# 1.net
KiCad netlist of a schematic drawn in Altium Designer
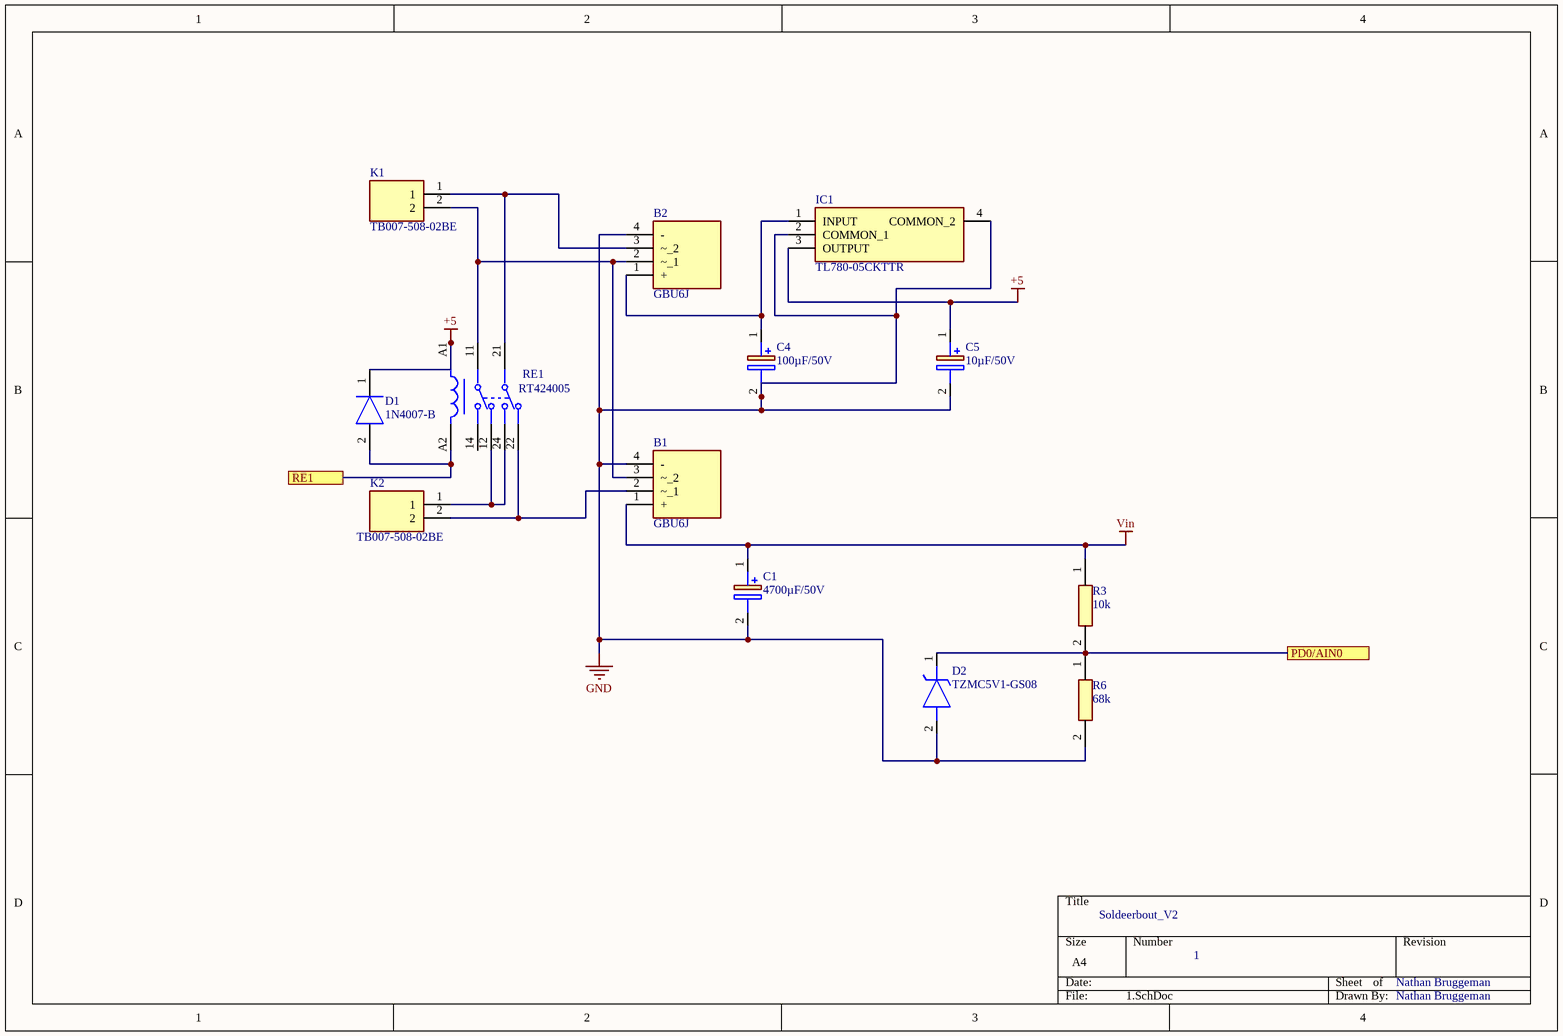
[diagram p0: 1.SchDoc]

(export (version "E")
  (design (tool "Eeschema 10.0.6"))
  (components
    (comp (ref "B1")
      (value "GBU6J")
      (footprint "GBU6J")
      (description "Bridge Rectifier")
      (libsource (lib "B1_B2") (part "GBU6J"))
    )
    (comp (ref "B2")
      (value "GBU6J")
      (footprint "GBU6J")
      (description "Bridge Rectifier")
      (libsource (lib "B1_B2") (part "GBU6J"))
    )
    (comp (ref "C1")
      (value "4700µF/50V")
      (footprint "CAPPRD1000W80D2200H3700")
      (description "Capacitor Polarised")
      (fields
        (field (name "MOUSER2 PART NUMBER") "80-ESK478M050AQ3AA")
        (field (name "MANUFACTURER_PART_NUMBER") "ESK478M050AQ3AA")
      )
      (libsource (lib "Condensator_4700µF_V2") (part "ESK478M050AQ3AA"))
    )
    (comp (ref "C4")
      (value "100µF/50V")
      (footprint "CAPPRD350W60D800H1250")
      (description "Capacitor Polarised")
      (fields (field (name "MANUFACTURER_PART_NUMBER") "ESK107M050AG3EA"))
      (libsource (lib "Condensator_100µF_V2") (part "ESK107M050AG3EA"))
    )
    (comp (ref "C5")
      (value "10µF/50V")
      (footprint "CAPPRD200W55D500H1200")
      (description "Capacitor Polarised")
      (fields
        (field (name "MOUSER2 PART NUMBER") "667-ECA-1HM100")
        (field (name "MANUFACTURER_PART_NUMBER") "ECA-1HM100")
      )
      (libsource (lib "Condensator_10µF_V2") (part "ECA-1HM100"))
    )
    (comp (ref "D1")
      (value "1N4007-B")
      (footprint "DIOAD1410W90L470D235")
      (description "Diode")
      (libsource (lib "D1") (part "1N4007-B"))
    )
    (comp (ref "D2")
      (value "TZMC5V1-GS08")
      (footprint "TZMC5V1GS08")
      (description "Zener Diode")
      (libsource (lib "D2") (part "TZMC5V1-GS08"))
    )
    (comp (ref "IC1")
      (value "TL780-05CKTTR")
      (footprint "TL78005CKTTR")
      (description "Integrated Circuit")
      (libsource (lib "IC1") (part "TL780-05CKTTR"))
    )
    (comp (ref "K1")
      (value "TB007-508-02BE")
      (footprint "TB00750802BE")
      (description "Connector")
      (fields (field (name "MOUSER2 PART NUMBER") "490-TB007-508-02BE"))
      (libsource (lib "K1_K2_K3_K8") (part "TB007-508-02BE"))
    )
    (comp (ref "K2")
      (value "TB007-508-02BE")
      (footprint "TB00750802BE")
      (description "Connector")
      (fields (field (name "MOUSER2 PART NUMBER") "490-TB007-508-02BE"))
      (libsource (lib "K1_K2_K3_K8") (part "TB007-508-02BE"))
    )
    (comp (ref "R3")
      (value "10k")
      (footprint "0805")
      (description "Resistor")
      (fields (field (name "MANUFACTURER_PART_NUMBER") "CFN0805-FZ-R030ELF"))
      (libsource (lib "Weerstand_0805") (part "CFN0805-FZ-R030ELF"))
    )
    (comp (ref "R6")
      (value "68k")
      (footprint "0805")
      (description "Resistor")
      (fields (field (name "MANUFACTURER_PART_NUMBER") "CFN0805-FZ-R030ELF"))
      (libsource (lib "Weerstand_0805") (part "CFN0805-FZ-R030ELF"))
    )
    (comp (ref "RE1")
      (value "RT424005")
      (footprint "FP-RT424005-MFG")
      (description "RELAY GENERAL PURPOSE DPDT 8A 5V")
      (fields
        (field (name "OCTOPART") "https://octopart.com/5-1393243-9-te+connectivity-41835766")
        (field (name "MANUFACTURER") "TE Connectivity")
      )
      (libsource (lib "Altium Content Vault") (part "41b11f646d56a8146f21bf1e8c88c79"))
    )
  )
  (nets
    (net (code "1") (name "+5") (class "Default")
      (node (ref "C5") (pin "1") (pinfunction "+_1") (pintype "passive"))
      (node (ref "D1") (pin "1") (pinfunction "K_1") (pintype "passive"))
      (node (ref "IC1") (pin "3") (pinfunction "OUTPUT_3") (pintype "passive"))
      (node (ref "RE1") (pin "A1") (pinfunction "A1_A1") (pintype "passive"))
    )
    (net (code "2") (name "/PD0{slash}AIN0") (class "Default")
      (node (ref "D2") (pin "1") (pinfunction "K_1") (pintype "passive"))
      (node (ref "R3") (pin "2") (pinfunction "2_2") (pintype "passive"))
      (node (ref "R6") (pin "1") (pinfunction "1_1") (pintype "passive"))
    )
    (net (code "3") (name "/RE1") (class "Default")
      (node (ref "D1") (pin "2") (pinfunction "A_2") (pintype "passive"))
      (node (ref "RE1") (pin "A2") (pinfunction "A2_A2") (pintype "passive"))
    )
    (net (code "4") (name "GND") (class "Default")
      (node (ref "B1") (pin "4") (pinfunction "-_4") (pintype "passive"))
      (node (ref "B2") (pin "4") (pinfunction "-_4") (pintype "passive"))
      (node (ref "C1") (pin "2") (pinfunction "-_2") (pintype "passive"))
      (node (ref "C4") (pin "2") (pinfunction "-_2") (pintype "passive"))
      (node (ref "C5") (pin "2") (pinfunction "-_2") (pintype "passive"))
      (node (ref "D2") (pin "2") (pinfunction "A_2") (pintype "passive"))
      (node (ref "IC1") (pin "2") (pinfunction "COMMON_1_2") (pintype "passive"))
      (node (ref "IC1") (pin "4") (pinfunction "COMMON_2_4") (pintype "passive"))
      (node (ref "R6") (pin "2") (pinfunction "2_2") (pintype "passive"))
    )
    (net (code "5") (name "Net-(B1-~_1)") (class "Default")
      (node (ref "B1") (pin "2") (pinfunction "~_1_2") (pintype "passive"))
      (node (ref "K2") (pin "2") (pinfunction "2_2") (pintype "passive"))
      (node (ref "RE1") (pin "22") (pinfunction "22_22") (pintype "passive"))
    )
    (net (code "6") (name "Net-(B1-~_2)") (class "Default")
      (node (ref "B1") (pin "3") (pinfunction "~_2_3") (pintype "passive"))
      (node (ref "B2") (pin "2") (pinfunction "~_1_2") (pintype "passive"))
      (node (ref "K1") (pin "2") (pinfunction "2_2") (pintype "passive"))
      (node (ref "RE1") (pin "11") (pinfunction "11_11") (pintype "passive"))
    )
    (net (code "7") (name "Net-(B2-+)") (class "Default")
      (node (ref "B2") (pin "1") (pinfunction "+_1") (pintype "passive"))
      (node (ref "C4") (pin "1") (pinfunction "+_1") (pintype "passive"))
      (node (ref "IC1") (pin "1") (pinfunction "INPUT_1") (pintype "passive"))
    )
    (net (code "8") (name "Net-(B2-~_2)") (class "Default")
      (node (ref "B2") (pin "3") (pinfunction "~_2_3") (pintype "passive"))
      (node (ref "K1") (pin "1") (pinfunction "1_1") (pintype "passive"))
      (node (ref "RE1") (pin "21") (pinfunction "21_21") (pintype "passive"))
    )
    (net (code "9") (name "Net-(K2-Pad1)") (class "Default")
      (node (ref "K2") (pin "1") (pinfunction "1_1") (pintype "passive"))
      (node (ref "RE1") (pin "12") (pinfunction "12_12") (pintype "passive"))
      (node (ref "RE1") (pin "24") (pinfunction "24_24") (pintype "passive"))
    )
    (net (code "10") (name "Vin") (class "Default")
      (node (ref "B1") (pin "1") (pinfunction "+_1") (pintype "passive"))
      (node (ref "C1") (pin "1") (pinfunction "+_1") (pintype "passive"))
      (node (ref "R3") (pin "1") (pinfunction "1_1") (pintype "passive"))
    )
    (net (code "11") (name "unconnected-(RE1-Pad14)") (class "Default")
      (node (ref "RE1") (pin "14") (pinfunction "14_14") (pintype "passive"))
    )
  )
)
